# Sheet1-driver.net
KiCad netlist of a schematic drawn in Altium Designer
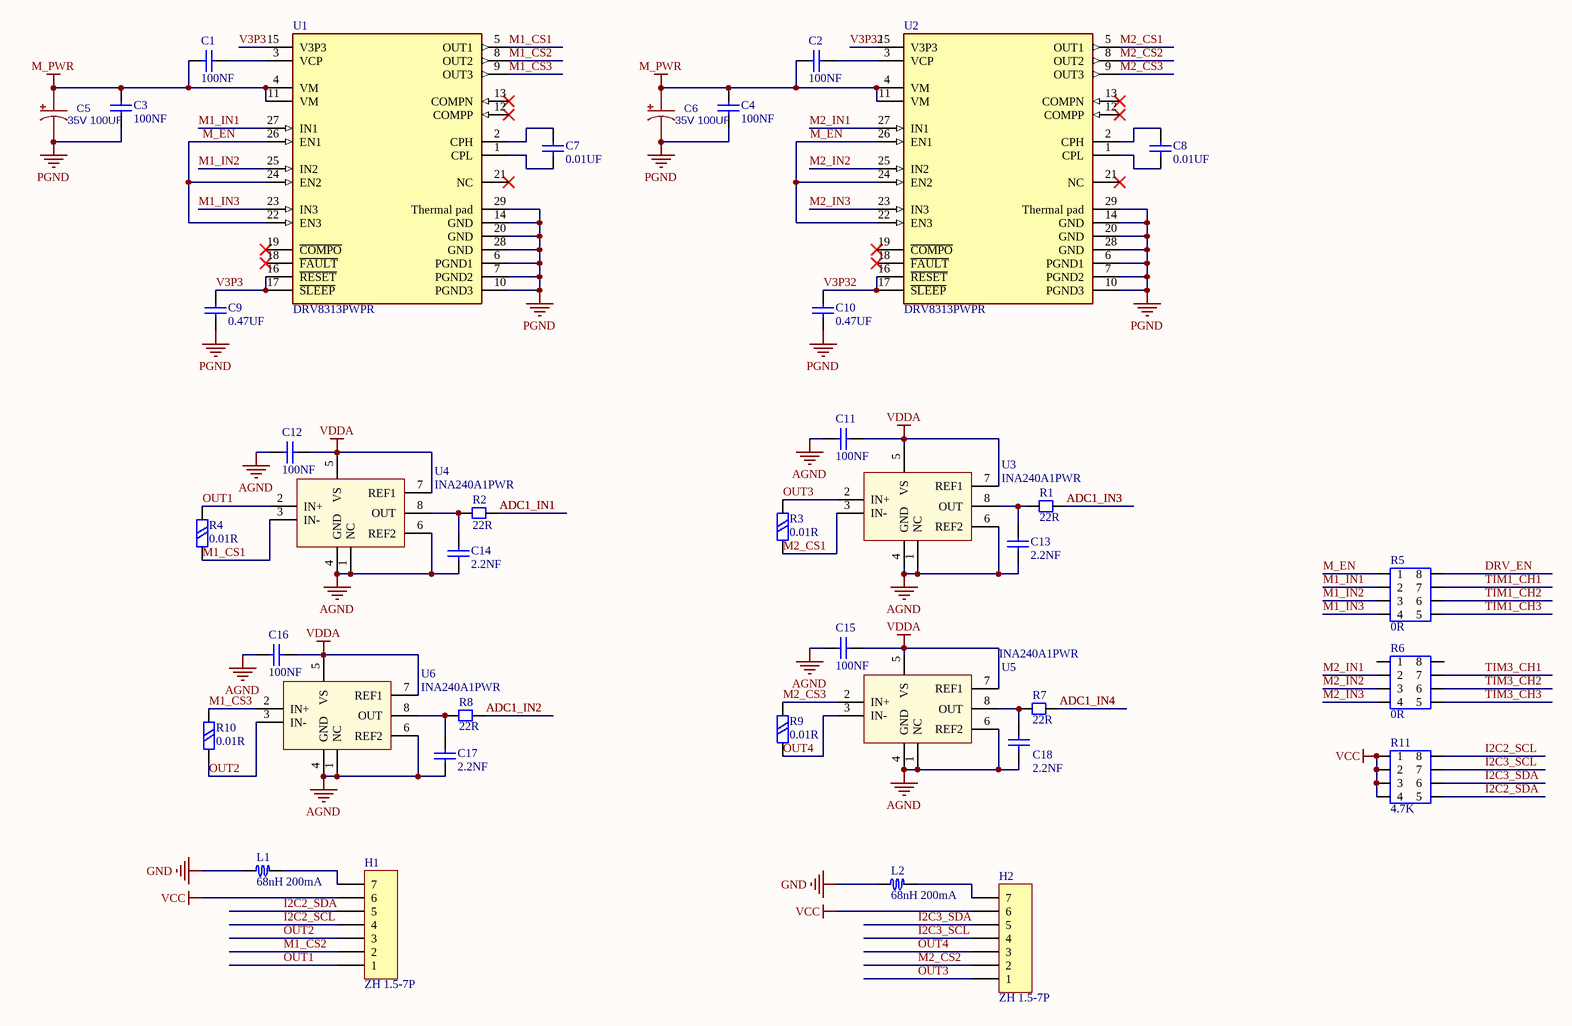
[diagram p0: Sheet1-driver.SchDoc]

(export (version "E")
  (design (tool "Eeschema 10.0.6"))
  (components
    (comp (ref "C1")
      (value "100NF")
      (footprint "CC1608-0603")
      (description "0603封装的电容")
      (fields (field (name "PUBLISHER") "Altium Limited"))
      (libsource (lib "base") (part "Cap Chip 0603"))
    )
    (comp (ref "C2")
      (value "100NF")
      (footprint "CC1608-0603")
      (description "0603封装的电容")
      (fields (field (name "PUBLISHER") "Altium Limited"))
      (libsource (lib "base") (part "Cap Chip 0603"))
    )
    (comp (ref "C3")
      (value "100NF")
      (footprint "CC1608-0603")
      (description "0603封装的电容")
      (fields (field (name "PUBLISHER") "Altium Limited"))
      (libsource (lib "base") (part "Cap Chip 0603"))
    )
    (comp (ref "C4")
      (value "100NF")
      (footprint "CC1608-0603")
      (description "0603封装的电容")
      (fields (field (name "PUBLISHER") "Altium Limited"))
      (libsource (lib "base") (part "Cap Chip 0603"))
    )
    (comp (ref "C5")
      (value "35V 100UF")
      (footprint "CAP-SMD_D6.3")
      (description "铝点解电容")
      (fields
        (field (name "BOM_SUPPLIER PART") "C413527")
        (field (name "BOM_MANUFACTURER PART") "EEEFP1C681AP")
        (field (name "CONTRIBUTOR") "LCSC")
      )
      (libsource (lib "base") (part "Cap ECAP SMD"))
    )
    (comp (ref "C6")
      (value "35V 100UF")
      (footprint "CAP-SMD_D6.3")
      (description "铝点解电容")
      (fields
        (field (name "BOM_SUPPLIER PART") "C413527")
        (field (name "BOM_MANUFACTURER PART") "EEEFP1C681AP")
        (field (name "CONTRIBUTOR") "LCSC")
      )
      (libsource (lib "base") (part "Cap ECAP SMD"))
    )
    (comp (ref "C7")
      (value "0.01UF")
      (footprint "CC1608-0603")
      (description "0603封装的电容")
      (fields (field (name "PUBLISHER") "Altium Limited"))
      (libsource (lib "base") (part "Cap Chip 0603"))
    )
    (comp (ref "C8")
      (value "0.01UF")
      (footprint "CC1608-0603")
      (description "0603封装的电容")
      (fields (field (name "PUBLISHER") "Altium Limited"))
      (libsource (lib "base") (part "Cap Chip 0603"))
    )
    (comp (ref "C9")
      (value "0.47UF")
      (footprint "CC1608-0603")
      (description "0603封装的电容")
      (fields (field (name "PUBLISHER") "Altium Limited"))
      (libsource (lib "base") (part "Cap Chip 0603"))
    )
    (comp (ref "C10")
      (value "0.47UF")
      (footprint "CC1608-0603")
      (description "0603封装的电容")
      (fields (field (name "PUBLISHER") "Altium Limited"))
      (libsource (lib "base") (part "Cap Chip 0603"))
    )
    (comp (ref "C11")
      (value "100NF")
      (footprint "CC1608-0603")
      (description "0603封装的电容")
      (fields (field (name "PUBLISHER") "Altium Limited"))
      (libsource (lib "base") (part "Cap Chip 0603"))
    )
    (comp (ref "C12")
      (value "100NF")
      (footprint "CC1608-0603")
      (description "0603封装的电容")
      (fields (field (name "PUBLISHER") "Altium Limited"))
      (libsource (lib "base") (part "Cap Chip 0603"))
    )
    (comp (ref "C13")
      (value "2.2NF")
      (footprint "CC1608-0603")
      (description "0603封装的电容")
      (fields (field (name "PUBLISHER") "Altium Limited"))
      (libsource (lib "base") (part "Cap Chip 0603"))
    )
    (comp (ref "C14")
      (value "2.2NF")
      (footprint "CC1608-0603")
      (description "0603封装的电容")
      (fields (field (name "PUBLISHER") "Altium Limited"))
      (libsource (lib "base") (part "Cap Chip 0603"))
    )
    (comp (ref "C15")
      (value "100NF")
      (footprint "CC1608-0603")
      (description "0603封装的电容")
      (fields (field (name "PUBLISHER") "Altium Limited"))
      (libsource (lib "base") (part "Cap Chip 0603"))
    )
    (comp (ref "C16")
      (value "100NF")
      (footprint "CC1608-0603")
      (description "0603封装的电容")
      (fields (field (name "PUBLISHER") "Altium Limited"))
      (libsource (lib "base") (part "Cap Chip 0603"))
    )
    (comp (ref "C17")
      (value "2.2NF")
      (footprint "CC1608-0603")
      (description "0603封装的电容")
      (fields (field (name "PUBLISHER") "Altium Limited"))
      (libsource (lib "base") (part "Cap Chip 0603"))
    )
    (comp (ref "C18")
      (value "2.2NF")
      (footprint "CC1608-0603")
      (description "0603封装的电容")
      (fields (field (name "PUBLISHER") "Altium Limited"))
      (libsource (lib "base") (part "Cap Chip 0603"))
    )
    (comp (ref "H1")
      (value "ZH 1.5-7P")
      (footprint "ZH1.5-7P")
      (description "ZH1.5-7P 间距1.5的贴片连接座")
      (libsource (lib "Connectors") (part "ZH 1.5-7P"))
    )
    (comp (ref "H2")
      (value "ZH 1.5-7P")
      (footprint "ZH1.5-7P")
      (description "ZH1.5-7P 间距1.5的贴片连接座")
      (libsource (lib "Connectors") (part "ZH 1.5-7P"))
    )
    (comp (ref "L1")
      (value "68nH 200mA")
      (footprint "Inductor-0603")
      (description "贴片电感 0603封装")
      (libsource (lib "base") (part "Inductor-0603"))
    )
    (comp (ref "L2")
      (value "68nH 200mA")
      (footprint "Inductor-0603")
      (description "贴片电感 0603封装")
      (libsource (lib "base") (part "Inductor-0603"))
    )
    (comp (ref "R1")
      (value "22R")
      (footprint "CR1608-0603")
      (description "0603封装电阻")
      (fields (field (name "PUBLISHER") "Altium Limited"))
      (libsource (lib "base") (part "Resistor Chip 0603"))
    )
    (comp (ref "R2")
      (value "22R")
      (footprint "CR1608-0603")
      (description "0603封装电阻")
      (fields (field (name "PUBLISHER") "Altium Limited"))
      (libsource (lib "base") (part "Resistor Chip 0603"))
    )
    (comp (ref "R3")
      (value "0.01R")
      (footprint "CR3216-1206")
      (description "1206封装电阻")
      (fields (field (name "PUBLISHER") "Altium Limited"))
      (libsource (lib "base") (part "Resistor Chip 1206"))
    )
    (comp (ref "R4")
      (value "0.01R")
      (footprint "CR3216-1206")
      (description "1206封装电阻")
      (fields (field (name "PUBLISHER") "Altium Limited"))
      (libsource (lib "base") (part "Resistor Chip 1206"))
    )
    (comp (ref "R5")
      (value "0R")
      (footprint "SMD_0603-8P")
      (description "0603封装电阻")
      (fields (field (name "PUBLISHER") "Altium Limited"))
      (libsource (lib "base") (part "Resistor Chip 0603_1206"))
    )
    (comp (ref "R6")
      (value "0R")
      (footprint "SMD_0603-8P")
      (description "0603封装电阻")
      (fields (field (name "PUBLISHER") "Altium Limited"))
      (libsource (lib "base") (part "Resistor Chip 0603_1206"))
    )
    (comp (ref "R7")
      (value "22R")
      (footprint "CR1608-0603")
      (description "0603封装电阻")
      (fields (field (name "PUBLISHER") "Altium Limited"))
      (libsource (lib "base") (part "Resistor Chip 0603"))
    )
    (comp (ref "R8")
      (value "22R")
      (footprint "CR1608-0603")
      (description "0603封装电阻")
      (fields (field (name "PUBLISHER") "Altium Limited"))
      (libsource (lib "base") (part "Resistor Chip 0603"))
    )
    (comp (ref "R9")
      (value "0.01R")
      (footprint "CR3216-1206")
      (description "1206封装电阻")
      (fields (field (name "PUBLISHER") "Altium Limited"))
      (libsource (lib "base") (part "Resistor Chip 1206"))
    )
    (comp (ref "R10")
      (value "0.01R")
      (footprint "CR3216-1206")
      (description "1206封装电阻")
      (fields (field (name "PUBLISHER") "Altium Limited"))
      (libsource (lib "base") (part "Resistor Chip 1206"))
    )
    (comp (ref "R11")
      (value "4.7K")
      (footprint "SMD_0603-8P")
      (description "0603封装电阻")
      (fields (field (name "PUBLISHER") "Altium Limited"))
      (libsource (lib "base") (part "Resistor Chip 0603_1206"))
    )
    (comp (ref "U1")
      (value "DRV8313PWPR")
      (footprint "HTSSOP-28")
      (description "独立控制的半 H 桥驱动器,主要用于驱动一个三项无刷电机IC MOTOR DRIVER 8V-60V 28HTSSOP")
      (libsource (lib "PB-Chip") (part "DRV8313"))
    )
    (comp (ref "U2")
      (value "DRV8313PWPR")
      (footprint "HTSSOP-28")
      (description "独立控制的半 H 桥驱动器,主要用于驱动一个三项无刷电机IC MOTOR DRIVER 8V-60V 28HTSSOP")
      (libsource (lib "PB-Chip") (part "DRV8313"))
    )
    (comp (ref "U3")
      (value "INA240A1PWR")
      (footprint "TSSOP-8")
      (description "超精密电流检测放大器")
      (libsource (lib "power-chip") (part "INA240A1PWR"))
    )
    (comp (ref "U4")
      (value "INA240A1PWR")
      (footprint "TSSOP-8")
      (description "超精密电流检测放大器")
      (libsource (lib "power-chip") (part "INA240A1PWR"))
    )
    (comp (ref "U5")
      (value "INA240A1PWR")
      (footprint "TSSOP-8")
      (description "超精密电流检测放大器")
      (libsource (lib "power-chip") (part "INA240A1PWR"))
    )
    (comp (ref "U6")
      (value "INA240A1PWR")
      (footprint "TSSOP-8")
      (description "超精密电流检测放大器")
      (libsource (lib "power-chip") (part "INA240A1PWR"))
    )
  )
  (nets
    (net (code "1") (name "/ADC1_IN1") (class "Default")
      (node (ref "R2") (pin "1") (pinfunction "1_1") (pintype "passive"))
    )
    (net (code "2") (name "/ADC1_IN2") (class "Default")
      (node (ref "R8") (pin "1") (pinfunction "1_1") (pintype "passive"))
    )
    (net (code "3") (name "/ADC1_IN3") (class "Default")
      (node (ref "R1") (pin "1") (pinfunction "1_1") (pintype "passive"))
    )
    (net (code "4") (name "/ADC1_IN4") (class "Default")
      (node (ref "R7") (pin "1") (pinfunction "1_1") (pintype "passive"))
    )
    (net (code "5") (name "/DRV_EN") (class "Default")
      (node (ref "R5") (pin "8") (pinfunction "8_8") (pintype "passive"))
    )
    (net (code "6") (name "/I2C2_SCL") (class "Default")
      (node (ref "H1") (pin "4") (pinfunction "4_4") (pintype "passive"))
      (node (ref "R11") (pin "8") (pinfunction "8_8") (pintype "passive"))
    )
    (net (code "7") (name "/I2C2_SDA") (class "Default")
      (node (ref "H1") (pin "5") (pinfunction "5_5") (pintype "passive"))
      (node (ref "R11") (pin "5") (pinfunction "5_5") (pintype "passive"))
    )
    (net (code "8") (name "/I2C3_SCL") (class "Default")
      (node (ref "H2") (pin "4") (pinfunction "4_4") (pintype "passive"))
      (node (ref "R11") (pin "7") (pinfunction "7_7") (pintype "passive"))
    )
    (net (code "9") (name "/I2C3_SDA") (class "Default")
      (node (ref "H2") (pin "5") (pinfunction "5_5") (pintype "passive"))
      (node (ref "R11") (pin "6") (pinfunction "6_6") (pintype "passive"))
    )
    (net (code "10") (name "/M1_CS1") (class "Default")
      (node (ref "R4") (pin "1") (pinfunction "1_1") (pintype "passive"))
      (node (ref "U1") (pin "5") (pinfunction "OUT1_5") (pintype "output"))
      (node (ref "U4") (pin "3") (pinfunction "IN-_3") (pintype "passive"))
    )
    (net (code "11") (name "/M1_CS2") (class "Default")
      (node (ref "H1") (pin "2") (pinfunction "2_2") (pintype "passive"))
      (node (ref "U1") (pin "8") (pinfunction "OUT2_8") (pintype "output"))
    )
    (net (code "12") (name "/M1_CS3") (class "Default")
      (node (ref "R10") (pin "2") (pinfunction "2_2") (pintype "passive"))
      (node (ref "U1") (pin "9") (pinfunction "OUT3_9") (pintype "output"))
      (node (ref "U6") (pin "2") (pinfunction "IN+_2") (pintype "passive"))
    )
    (net (code "13") (name "/M1_IN1") (class "Default")
      (node (ref "R5") (pin "2") (pinfunction "2_2") (pintype "passive"))
      (node (ref "U1") (pin "27") (pinfunction "IN1_27") (pintype "input"))
    )
    (net (code "14") (name "/M1_IN2") (class "Default")
      (node (ref "R5") (pin "3") (pinfunction "3_3") (pintype "passive"))
      (node (ref "U1") (pin "25") (pinfunction "IN2_25") (pintype "input"))
    )
    (net (code "15") (name "/M1_IN3") (class "Default")
      (node (ref "R5") (pin "4") (pinfunction "4_4") (pintype "passive"))
      (node (ref "U1") (pin "23") (pinfunction "IN3_23") (pintype "input"))
    )
    (net (code "16") (name "/M2_CS1") (class "Default")
      (node (ref "R3") (pin "1") (pinfunction "1_1") (pintype "passive"))
      (node (ref "U2") (pin "5") (pinfunction "OUT1_5") (pintype "output"))
      (node (ref "U3") (pin "3") (pinfunction "IN-_3") (pintype "passive"))
    )
    (net (code "17") (name "/M2_CS2") (class "Default")
      (node (ref "H2") (pin "2") (pinfunction "2_2") (pintype "passive"))
      (node (ref "U2") (pin "8") (pinfunction "OUT2_8") (pintype "output"))
    )
    (net (code "18") (name "/M2_CS3") (class "Default")
      (node (ref "R9") (pin "2") (pinfunction "2_2") (pintype "passive"))
      (node (ref "U2") (pin "9") (pinfunction "OUT3_9") (pintype "output"))
      (node (ref "U5") (pin "2") (pinfunction "IN+_2") (pintype "passive"))
    )
    (net (code "19") (name "/M2_IN1") (class "Default")
      (node (ref "R6") (pin "2") (pinfunction "2_2") (pintype "passive"))
      (node (ref "U2") (pin "27") (pinfunction "IN1_27") (pintype "input"))
    )
    (net (code "20") (name "/M2_IN2") (class "Default")
      (node (ref "R6") (pin "3") (pinfunction "3_3") (pintype "passive"))
      (node (ref "U2") (pin "25") (pinfunction "IN2_25") (pintype "input"))
    )
    (net (code "21") (name "/M2_IN3") (class "Default")
      (node (ref "R6") (pin "4") (pinfunction "4_4") (pintype "passive"))
      (node (ref "U2") (pin "23") (pinfunction "IN3_23") (pintype "input"))
    )
    (net (code "22") (name "/M_EN") (class "Default")
      (node (ref "R5") (pin "1") (pinfunction "1_1") (pintype "passive"))
      (node (ref "U1") (pin "22") (pinfunction "EN3_22") (pintype "input"))
      (node (ref "U1") (pin "24") (pinfunction "EN2_24") (pintype "input"))
      (node (ref "U1") (pin "26") (pinfunction "EN1_26") (pintype "input"))
      (node (ref "U2") (pin "22") (pinfunction "EN3_22") (pintype "input"))
      (node (ref "U2") (pin "24") (pinfunction "EN2_24") (pintype "input"))
      (node (ref "U2") (pin "26") (pinfunction "EN1_26") (pintype "input"))
    )
    (net (code "23") (name "/OUT1") (class "Default")
      (node (ref "H1") (pin "1") (pinfunction "1_1") (pintype "passive"))
      (node (ref "R4") (pin "2") (pinfunction "2_2") (pintype "passive"))
      (node (ref "U4") (pin "2") (pinfunction "IN+_2") (pintype "passive"))
    )
    (net (code "24") (name "/OUT2") (class "Default")
      (node (ref "H1") (pin "3") (pinfunction "3_3") (pintype "passive"))
      (node (ref "R10") (pin "1") (pinfunction "1_1") (pintype "passive"))
      (node (ref "U6") (pin "3") (pinfunction "IN-_3") (pintype "passive"))
    )
    (net (code "25") (name "/OUT3") (class "Default")
      (node (ref "H2") (pin "1") (pinfunction "1_1") (pintype "passive"))
      (node (ref "R3") (pin "2") (pinfunction "2_2") (pintype "passive"))
      (node (ref "U3") (pin "2") (pinfunction "IN+_2") (pintype "passive"))
    )
    (net (code "26") (name "/OUT4") (class "Default")
      (node (ref "H2") (pin "3") (pinfunction "3_3") (pintype "passive"))
      (node (ref "R9") (pin "1") (pinfunction "1_1") (pintype "passive"))
      (node (ref "U5") (pin "3") (pinfunction "IN-_3") (pintype "passive"))
    )
    (net (code "27") (name "/TIM1_CH1") (class "Default")
      (node (ref "R5") (pin "7") (pinfunction "7_7") (pintype "passive"))
    )
    (net (code "28") (name "/TIM1_CH2") (class "Default")
      (node (ref "R5") (pin "6") (pinfunction "6_6") (pintype "passive"))
    )
    (net (code "29") (name "/TIM1_CH3") (class "Default")
      (node (ref "R5") (pin "5") (pinfunction "5_5") (pintype "passive"))
    )
    (net (code "30") (name "/TIM3_CH1") (class "Default")
      (node (ref "R6") (pin "7") (pinfunction "7_7") (pintype "passive"))
    )
    (net (code "31") (name "/TIM3_CH2") (class "Default")
      (node (ref "R6") (pin "6") (pinfunction "6_6") (pintype "passive"))
    )
    (net (code "32") (name "/TIM3_CH3") (class "Default")
      (node (ref "R6") (pin "5") (pinfunction "5_5") (pintype "passive"))
    )
    (net (code "33") (name "/V3P3") (class "Default")
      (node (ref "C9") (pin "1") (pinfunction "1_1") (pintype "passive"))
      (node (ref "U1") (pin "15") (pinfunction "V3P3_15") (pintype "power_in"))
      (node (ref "U1") (pin "16") (pinfunction "~{RESET}_16") (pintype "passive"))
      (node (ref "U1") (pin "17") (pinfunction "~{SLEEP}_17") (pintype "passive"))
    )
    (net (code "34") (name "/V3P32") (class "Default")
      (node (ref "C10") (pin "1") (pinfunction "1_1") (pintype "passive"))
      (node (ref "U2") (pin "15") (pinfunction "V3P3_15") (pintype "power_in"))
      (node (ref "U2") (pin "16") (pinfunction "~{RESET}_16") (pintype "passive"))
      (node (ref "U2") (pin "17") (pinfunction "~{SLEEP}_17") (pintype "passive"))
    )
    (net (code "35") (name "AGND") (class "Default")
      (node (ref "C11") (pin "2") (pinfunction "2_2") (pintype "passive"))
      (node (ref "C12") (pin "2") (pinfunction "2_2") (pintype "passive"))
      (node (ref "C13") (pin "1") (pinfunction "1_1") (pintype "passive"))
      (node (ref "C14") (pin "1") (pinfunction "1_1") (pintype "passive"))
      (node (ref "C15") (pin "2") (pinfunction "2_2") (pintype "passive"))
      (node (ref "C16") (pin "2") (pinfunction "2_2") (pintype "passive"))
      (node (ref "C17") (pin "1") (pinfunction "1_1") (pintype "passive"))
      (node (ref "C18") (pin "1") (pinfunction "1_1") (pintype "passive"))
      (node (ref "U3") (pin "1") (pinfunction "NC_1") (pintype "passive"))
      (node (ref "U3") (pin "4") (pinfunction "GND_4") (pintype "passive"))
      (node (ref "U3") (pin "6") (pinfunction "REF2_6") (pintype "passive"))
      (node (ref "U4") (pin "1") (pinfunction "NC_1") (pintype "passive"))
      (node (ref "U4") (pin "4") (pinfunction "GND_4") (pintype "passive"))
      (node (ref "U4") (pin "6") (pinfunction "REF2_6") (pintype "passive"))
      (node (ref "U5") (pin "1") (pinfunction "NC_1") (pintype "passive"))
      (node (ref "U5") (pin "4") (pinfunction "GND_4") (pintype "passive"))
      (node (ref "U5") (pin "6") (pinfunction "REF2_6") (pintype "passive"))
      (node (ref "U6") (pin "1") (pinfunction "NC_1") (pintype "passive"))
      (node (ref "U6") (pin "4") (pinfunction "GND_4") (pintype "passive"))
      (node (ref "U6") (pin "6") (pinfunction "REF2_6") (pintype "passive"))
    )
    (net (code "36") (name "GND") (class "Default")
      (node (ref "L1") (pin "2") (pinfunction "2_2") (pintype "passive"))
      (node (ref "L2") (pin "2") (pinfunction "2_2") (pintype "passive"))
    )
    (net (code "37") (name "M_PWR") (class "Default")
      (node (ref "C1") (pin "2") (pinfunction "2_2") (pintype "passive"))
      (node (ref "C2") (pin "2") (pinfunction "2_2") (pintype "passive"))
      (node (ref "C3") (pin "1") (pinfunction "1_1") (pintype "passive"))
      (node (ref "C4") (pin "1") (pinfunction "1_1") (pintype "passive"))
      (node (ref "C5") (pin "1") (pinfunction "1_1") (pintype "passive"))
      (node (ref "C6") (pin "1") (pinfunction "1_1") (pintype "passive"))
      (node (ref "U1") (pin "11") (pinfunction "VM_11") (pintype "power_in"))
      (node (ref "U1") (pin "4") (pinfunction "VM_4") (pintype "power_in"))
      (node (ref "U2") (pin "11") (pinfunction "VM_11") (pintype "power_in"))
      (node (ref "U2") (pin "4") (pinfunction "VM_4") (pintype "power_in"))
    )
    (net (code "38") (name "Net-(H1-Pad7)") (class "Default")
      (node (ref "H1") (pin "7") (pinfunction "7_7") (pintype "passive"))
      (node (ref "L1") (pin "1") (pinfunction "1_1") (pintype "passive"))
    )
    (net (code "39") (name "Net-(H2-Pad7)") (class "Default")
      (node (ref "H2") (pin "7") (pinfunction "7_7") (pintype "passive"))
      (node (ref "L2") (pin "1") (pinfunction "1_1") (pintype "passive"))
    )
    (net (code "40") (name "Net-(U1-CPH)") (class "Default")
      (node (ref "C7") (pin "1") (pinfunction "1_1") (pintype "passive"))
      (node (ref "U1") (pin "2") (pinfunction "CPH_2") (pintype "power_in"))
    )
    (net (code "41") (name "Net-(U1-CPL)") (class "Default")
      (node (ref "C7") (pin "2") (pinfunction "2_2") (pintype "passive"))
      (node (ref "U1") (pin "1") (pinfunction "CPL_1") (pintype "power_in"))
    )
    (net (code "42") (name "Net-(U1-VCP)") (class "Default")
      (node (ref "C1") (pin "1") (pinfunction "1_1") (pintype "passive"))
      (node (ref "U1") (pin "3") (pinfunction "VCP_3") (pintype "power_in"))
    )
    (net (code "43") (name "Net-(U2-CPH)") (class "Default")
      (node (ref "C8") (pin "1") (pinfunction "1_1") (pintype "passive"))
      (node (ref "U2") (pin "2") (pinfunction "CPH_2") (pintype "power_in"))
    )
    (net (code "44") (name "Net-(U2-CPL)") (class "Default")
      (node (ref "C8") (pin "2") (pinfunction "2_2") (pintype "passive"))
      (node (ref "U2") (pin "1") (pinfunction "CPL_1") (pintype "power_in"))
    )
    (net (code "45") (name "Net-(U2-VCP)") (class "Default")
      (node (ref "C2") (pin "1") (pinfunction "1_1") (pintype "passive"))
      (node (ref "U2") (pin "3") (pinfunction "VCP_3") (pintype "power_in"))
    )
    (net (code "46") (name "Net-(U3-OUT)") (class "Default")
      (node (ref "C13") (pin "2") (pinfunction "2_2") (pintype "passive"))
      (node (ref "R1") (pin "2") (pinfunction "2_2") (pintype "passive"))
      (node (ref "U3") (pin "8") (pinfunction "OUT_8") (pintype "passive"))
    )
    (net (code "47") (name "Net-(U4-OUT)") (class "Default")
      (node (ref "C14") (pin "2") (pinfunction "2_2") (pintype "passive"))
      (node (ref "R2") (pin "2") (pinfunction "2_2") (pintype "passive"))
      (node (ref "U4") (pin "8") (pinfunction "OUT_8") (pintype "passive"))
    )
    (net (code "48") (name "Net-(U5-OUT)") (class "Default")
      (node (ref "C18") (pin "2") (pinfunction "2_2") (pintype "passive"))
      (node (ref "R7") (pin "2") (pinfunction "2_2") (pintype "passive"))
      (node (ref "U5") (pin "8") (pinfunction "OUT_8") (pintype "passive"))
    )
    (net (code "49") (name "Net-(U6-OUT)") (class "Default")
      (node (ref "C17") (pin "2") (pinfunction "2_2") (pintype "passive"))
      (node (ref "R8") (pin "2") (pinfunction "2_2") (pintype "passive"))
      (node (ref "U6") (pin "8") (pinfunction "OUT_8") (pintype "passive"))
    )
    (net (code "50") (name "PGND") (class "Default")
      (node (ref "C10") (pin "2") (pinfunction "2_2") (pintype "passive"))
      (node (ref "C3") (pin "2") (pinfunction "2_2") (pintype "passive"))
      (node (ref "C4") (pin "2") (pinfunction "2_2") (pintype "passive"))
      (node (ref "C5") (pin "2") (pinfunction "2_2") (pintype "passive"))
      (node (ref "C6") (pin "2") (pinfunction "2_2") (pintype "passive"))
      (node (ref "C9") (pin "2") (pinfunction "2_2") (pintype "passive"))
      (node (ref "U1") (pin "10") (pinfunction "PGND3_10") (pintype "power_in"))
      (node (ref "U1") (pin "14") (pinfunction "GND_14") (pintype "power_in"))
      (node (ref "U1") (pin "20") (pinfunction "GND_20") (pintype "power_in"))
      (node (ref "U1") (pin "28") (pinfunction "GND_28") (pintype "power_in"))
      (node (ref "U1") (pin "29") (pinfunction "Thermal_pad_29") (pintype "power_in"))
      (node (ref "U1") (pin "6") (pinfunction "PGND1_6") (pintype "power_in"))
      (node (ref "U1") (pin "7") (pinfunction "PGND2_7") (pintype "power_in"))
      (node (ref "U2") (pin "10") (pinfunction "PGND3_10") (pintype "power_in"))
      (node (ref "U2") (pin "14") (pinfunction "GND_14") (pintype "power_in"))
      (node (ref "U2") (pin "20") (pinfunction "GND_20") (pintype "power_in"))
      (node (ref "U2") (pin "28") (pinfunction "GND_28") (pintype "power_in"))
      (node (ref "U2") (pin "29") (pinfunction "Thermal_pad_29") (pintype "power_in"))
      (node (ref "U2") (pin "6") (pinfunction "PGND1_6") (pintype "power_in"))
      (node (ref "U2") (pin "7") (pinfunction "PGND2_7") (pintype "power_in"))
    )
    (net (code "51") (name "VCC") (class "Default")
      (node (ref "H1") (pin "6") (pinfunction "6_6") (pintype "passive"))
      (node (ref "H2") (pin "6") (pinfunction "6_6") (pintype "passive"))
      (node (ref "R11") (pin "1") (pinfunction "1_1") (pintype "passive"))
      (node (ref "R11") (pin "2") (pinfunction "2_2") (pintype "passive"))
      (node (ref "R11") (pin "3") (pinfunction "3_3") (pintype "passive"))
      (node (ref "R11") (pin "4") (pinfunction "4_4") (pintype "passive"))
    )
    (net (code "52") (name "VDDA") (class "Default")
      (node (ref "C11") (pin "1") (pinfunction "1_1") (pintype "passive"))
      (node (ref "C12") (pin "1") (pinfunction "1_1") (pintype "passive"))
      (node (ref "C15") (pin "1") (pinfunction "1_1") (pintype "passive"))
      (node (ref "C16") (pin "1") (pinfunction "1_1") (pintype "passive"))
      (node (ref "U3") (pin "5") (pinfunction "VS_5") (pintype "passive"))
      (node (ref "U3") (pin "7") (pinfunction "REF1_7") (pintype "passive"))
      (node (ref "U4") (pin "5") (pinfunction "VS_5") (pintype "passive"))
      (node (ref "U4") (pin "7") (pinfunction "REF1_7") (pintype "passive"))
      (node (ref "U5") (pin "5") (pinfunction "VS_5") (pintype "passive"))
      (node (ref "U5") (pin "7") (pinfunction "REF1_7") (pintype "passive"))
      (node (ref "U6") (pin "5") (pinfunction "VS_5") (pintype "passive"))
      (node (ref "U6") (pin "7") (pinfunction "REF1_7") (pintype "passive"))
    )
    (net (code "53") (name "unconnected-(R6-Pad1)") (class "Default")
      (node (ref "R6") (pin "1") (pinfunction "1_1") (pintype "passive"))
    )
    (net (code "54") (name "unconnected-(R6-Pad8)") (class "Default")
      (node (ref "R6") (pin "8") (pinfunction "8_8") (pintype "passive"))
    )
    (net (code "55") (name "unconnected-(U1-COMPN-Pad13)") (class "Default")
      (node (ref "U1") (pin "13") (pinfunction "COMPN_13") (pintype "input+no_connect"))
    )
    (net (code "56") (name "unconnected-(U1-COMPP-Pad12)") (class "Default")
      (node (ref "U1") (pin "12") (pinfunction "COMPP_12") (pintype "input+no_connect"))
    )
    (net (code "57") (name "unconnected-(U1-NC-Pad21)") (class "Default")
      (node (ref "U1") (pin "21") (pinfunction "NC_21") (pintype "passive+no_connect"))
    )
    (net (code "58") (name "unconnected-(U1-~{COMPO}-Pad19)") (class "Default")
      (node (ref "U1") (pin "19") (pinfunction "~{COMPO}_19") (pintype "open_collector+no_connect"))
    )
    (net (code "59") (name "unconnected-(U1-~{FAULT}-Pad18)") (class "Default")
      (node (ref "U1") (pin "18") (pinfunction "~{FAULT}_18") (pintype "open_collector+no_connect"))
    )
    (net (code "60") (name "unconnected-(U2-COMPN-Pad13)") (class "Default")
      (node (ref "U2") (pin "13") (pinfunction "COMPN_13") (pintype "input+no_connect"))
    )
    (net (code "61") (name "unconnected-(U2-COMPP-Pad12)") (class "Default")
      (node (ref "U2") (pin "12") (pinfunction "COMPP_12") (pintype "input+no_connect"))
    )
    (net (code "62") (name "unconnected-(U2-NC-Pad21)") (class "Default")
      (node (ref "U2") (pin "21") (pinfunction "NC_21") (pintype "passive+no_connect"))
    )
    (net (code "63") (name "unconnected-(U2-~{COMPO}-Pad19)") (class "Default")
      (node (ref "U2") (pin "19") (pinfunction "~{COMPO}_19") (pintype "open_collector+no_connect"))
    )
    (net (code "64") (name "unconnected-(U2-~{FAULT}-Pad18)") (class "Default")
      (node (ref "U2") (pin "18") (pinfunction "~{FAULT}_18") (pintype "open_collector+no_connect"))
    )
  )
)
